# MCU_144_POWER.net
KiCad netlist of a schematic drawn in Altium Designer
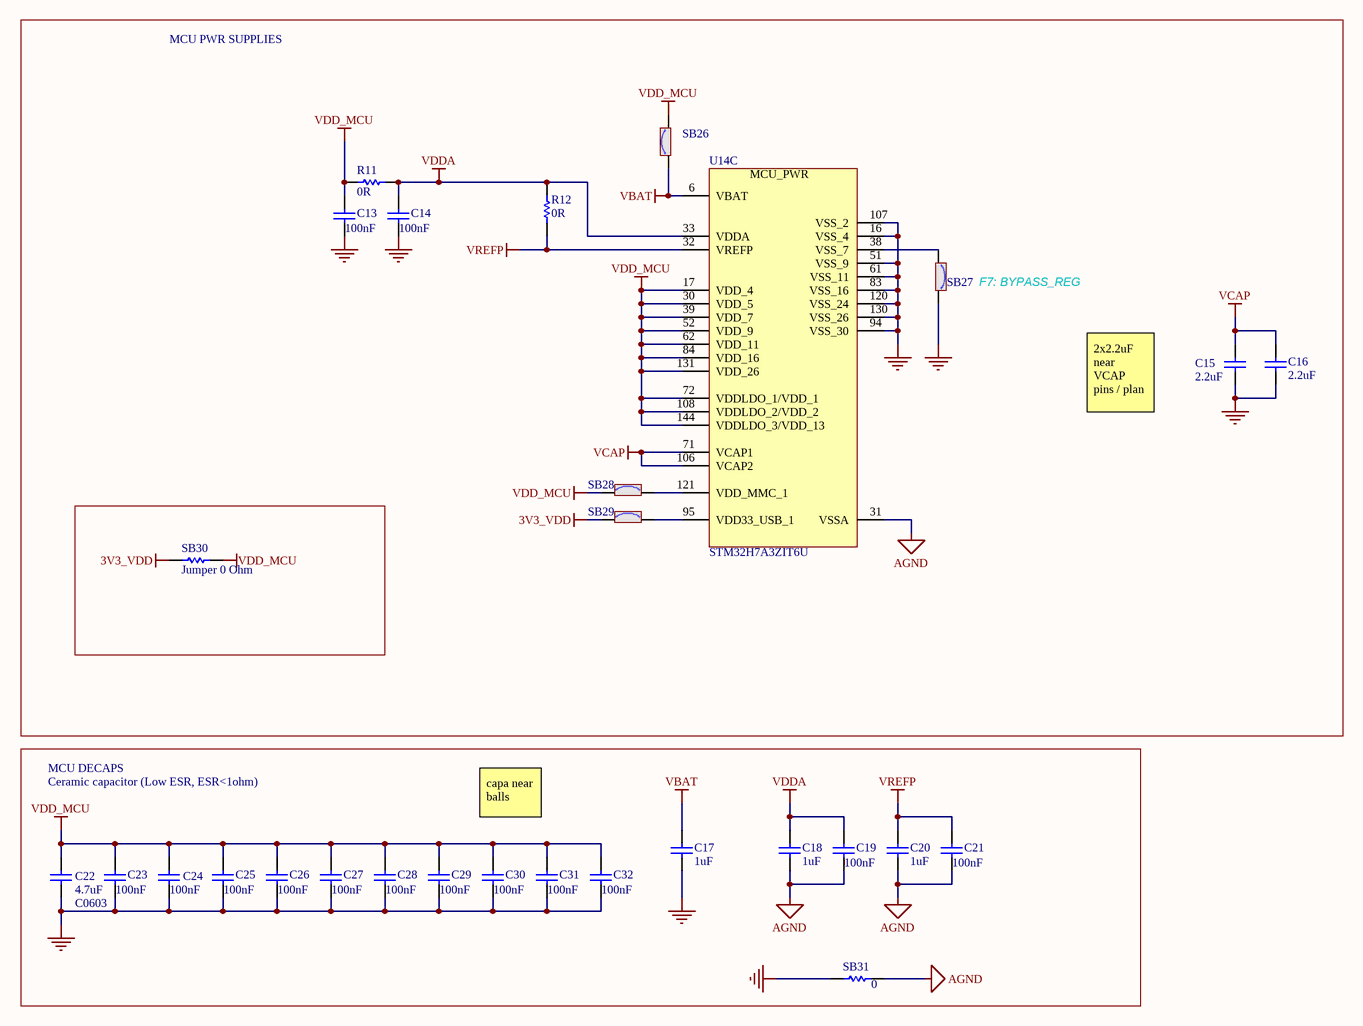
[diagram p0: MCU_144_POWER.SchDoc]

(export (version "E")
  (design (tool "Eeschema 10.0.6"))
  (components
    (comp (ref "C13")
      (value "Capacitor")
      (footprint "C0402")
      (description "CAP CER 0.1UF 16V X7R 0402")
      (fields
        (field (name "MANUFACTURER") "Yageo")
        (field (name "MANUFACTURER PART NUMBER") "CC0402KRX7R7BB104")
        (field (name "CAPACITANCE") "100nF")
      )
      (libsource (lib "MCD_PARTS_database") (part "Capacitor"))
    )
    (comp (ref "C14")
      (value "Capacitor")
      (footprint "C0402")
      (description "CAP CER 0.1UF 16V X7R 0402")
      (fields
        (field (name "MANUFACTURER") "Yageo")
        (field (name "MANUFACTURER PART NUMBER") "CC0402KRX7R7BB104")
        (field (name "CAPACITANCE") "100nF")
      )
      (libsource (lib "MCD_PARTS_database") (part "Capacitor"))
    )
    (comp (ref "C15")
      (value "2.2uF")
      (footprint "C0603")
      (description "Capacitor, MLCC, 2.2uF, 10V, X5R, 10%, 0603, T=0,8mm")
      (fields
        (field (name "INTERNAL_PART_NUMBER") "MCD-00012")
        (field (name "MANUFACTURER_PART_NUMBER") "CC0603KRX5R6BB225")
        (field (name "PROVIDED_BY") "SUBCO")
      )
      (libsource (lib "MCD_PARTS_database") (part "Capacitor"))
    )
    (comp (ref "C16")
      (value "2.2uF")
      (footprint "C0603")
      (description "Capacitor, MLCC, 2.2uF, 10V, X5R, 10%, 0603, T=0,8mm")
      (fields
        (field (name "INTERNAL_PART_NUMBER") "MCD-00012")
        (field (name "MANUFACTURER_PART_NUMBER") "CC0603KRX5R6BB225")
        (field (name "PROVIDED_BY") "SUBCO")
      )
      (libsource (lib "MCD_PARTS_database") (part "Capacitor"))
    )
    (comp (ref "C17")
      (value "1uF")
      (footprint "C0603")
      (description "Capacitor, MLCC, 1uF, 6V3, X5R, 10%, 0603, T=0,8mm")
      (fields
        (field (name "INTERNAL_PART_NUMBER") "MCD-00238")
        (field (name "MANUFACTURER_PART_NUMBER") "CC0603KRX5R5BB105")
        (field (name "PROVIDED_BY") "SUBCO")
      )
      (libsource (lib "MCD_PARTS_database") (part "Capacitor"))
    )
    (comp (ref "C18")
      (value "1uF")
      (footprint "C0603")
      (description "Capacitor, MLCC, 1uF, 6V3, X5R, 10%, 0603, T=0,8mm")
      (fields
        (field (name "INTERNAL_PART_NUMBER") "MCD-00238")
        (field (name "MANUFACTURER_PART_NUMBER") "CC0603KRX5R5BB105")
        (field (name "PROVIDED_BY") "SUBCO")
      )
      (libsource (lib "MCD_PARTS_database") (part "Capacitor"))
    )
    (comp (ref "C19")
      (value "Capacitor")
      (footprint "C0402")
      (description "CAP CER 0.1UF 16V X7R 0402")
      (fields
        (field (name "MANUFACTURER") "Yageo")
        (field (name "MANUFACTURER PART NUMBER") "CC0402KRX7R7BB104")
        (field (name "CAPACITANCE") "100nF")
      )
      (libsource (lib "MCD_PARTS_database") (part "Capacitor"))
    )
    (comp (ref "C20")
      (value "1uF")
      (footprint "C0603")
      (description "Capacitor, MLCC, 1uF, 6V3, X5R, 10%, 0603, T=0,8mm")
      (fields
        (field (name "INTERNAL_PART_NUMBER") "MCD-00238")
        (field (name "MANUFACTURER_PART_NUMBER") "CC0603KRX5R5BB105")
        (field (name "PROVIDED_BY") "SUBCO")
      )
      (libsource (lib "MCD_PARTS_database") (part "Capacitor"))
    )
    (comp (ref "C21")
      (value "Capacitor")
      (footprint "C0402")
      (description "CAP CER 0.1UF 16V X7R 0402")
      (fields
        (field (name "MANUFACTURER") "Yageo")
        (field (name "MANUFACTURER PART NUMBER") "CC0402KRX7R7BB104")
        (field (name "CAPACITANCE") "100nF")
      )
      (libsource (lib "MCD_PARTS_database") (part "Capacitor"))
    )
    (comp (ref "C22")
      (value "4.7uF")
      (footprint "C0603")
      (description "Capacitor, MLCC, 4.7µF, 10V, X5R, 20%, 0603, T=0,8mm")
      (fields
        (field (name "INTERNAL_PART_NUMBER") "MCD-01121")
        (field (name "MANUFACTURER_PART_NUMBER") "GRM188R61A475ME15")
        (field (name "PACKAGE") "C0603")
        (field (name "PROVIDED_BY") "SUBCO")
      )
      (libsource (lib "MCD_PARTS_database") (part "Capacitor"))
    )
    (comp (ref "C23")
      (value "Capacitor")
      (footprint "C0402")
      (description "CAP CER 0.1UF 16V X7R 0402")
      (fields
        (field (name "MANUFACTURER") "Yageo")
        (field (name "MANUFACTURER PART NUMBER") "CC0402KRX7R7BB104")
        (field (name "CAPACITANCE") "100nF")
      )
      (libsource (lib "MCD_PARTS_database") (part "Capacitor"))
    )
    (comp (ref "C24")
      (value "Capacitor")
      (footprint "C0402")
      (description "CAP CER 0.1UF 16V X7R 0402")
      (fields
        (field (name "MANUFACTURER") "Yageo")
        (field (name "MANUFACTURER PART NUMBER") "CC0402KRX7R7BB104")
        (field (name "CAPACITANCE") "100nF")
      )
      (libsource (lib "MCD_PARTS_database") (part "Capacitor"))
    )
    (comp (ref "C25")
      (value "Capacitor")
      (footprint "C0402")
      (description "CAP CER 0.1UF 16V X7R 0402")
      (fields
        (field (name "MANUFACTURER") "Yageo")
        (field (name "MANUFACTURER PART NUMBER") "CC0402KRX7R7BB104")
        (field (name "CAPACITANCE") "100nF")
      )
      (libsource (lib "MCD_PARTS_database") (part "Capacitor"))
    )
    (comp (ref "C26")
      (value "Capacitor")
      (footprint "C0402")
      (description "CAP CER 0.1UF 16V X7R 0402")
      (fields
        (field (name "MANUFACTURER") "Yageo")
        (field (name "MANUFACTURER PART NUMBER") "CC0402KRX7R7BB104")
        (field (name "CAPACITANCE") "100nF")
      )
      (libsource (lib "MCD_PARTS_database") (part "Capacitor"))
    )
    (comp (ref "C27")
      (value "Capacitor")
      (footprint "C0402")
      (description "CAP CER 0.1UF 16V X7R 0402")
      (fields
        (field (name "MANUFACTURER") "Yageo")
        (field (name "MANUFACTURER PART NUMBER") "CC0402KRX7R7BB104")
        (field (name "CAPACITANCE") "100nF")
      )
      (libsource (lib "MCD_PARTS_database") (part "Capacitor"))
    )
    (comp (ref "C28")
      (value "Capacitor")
      (footprint "C0402")
      (description "CAP CER 0.1UF 16V X7R 0402")
      (fields
        (field (name "MANUFACTURER") "Yageo")
        (field (name "MANUFACTURER PART NUMBER") "CC0402KRX7R7BB104")
        (field (name "CAPACITANCE") "100nF")
      )
      (libsource (lib "MCD_PARTS_database") (part "Capacitor"))
    )
    (comp (ref "C29")
      (value "Capacitor")
      (footprint "C0402")
      (description "CAP CER 0.1UF 16V X7R 0402")
      (fields
        (field (name "MANUFACTURER") "Yageo")
        (field (name "MANUFACTURER PART NUMBER") "CC0402KRX7R7BB104")
        (field (name "CAPACITANCE") "100nF")
      )
      (libsource (lib "MCD_PARTS_database") (part "Capacitor"))
    )
    (comp (ref "C30")
      (value "Capacitor")
      (footprint "C0402")
      (description "CAP CER 0.1UF 16V X7R 0402")
      (fields
        (field (name "MANUFACTURER") "Yageo")
        (field (name "MANUFACTURER PART NUMBER") "CC0402KRX7R7BB104")
        (field (name "CAPACITANCE") "100nF")
      )
      (libsource (lib "MCD_PARTS_database") (part "Capacitor"))
    )
    (comp (ref "C31")
      (value "Capacitor")
      (footprint "C0402")
      (description "CAP CER 0.1UF 16V X7R 0402")
      (fields
        (field (name "MANUFACTURER") "Yageo")
        (field (name "MANUFACTURER PART NUMBER") "CC0402KRX7R7BB104")
        (field (name "CAPACITANCE") "100nF")
      )
      (libsource (lib "MCD_PARTS_database") (part "Capacitor"))
    )
    (comp (ref "C32")
      (value "Capacitor")
      (footprint "C0402")
      (description "CAP CER 0.1UF 16V X7R 0402")
      (fields
        (field (name "MANUFACTURER") "Yageo")
        (field (name "MANUFACTURER PART NUMBER") "CC0402KRX7R7BB104")
        (field (name "CAPACITANCE") "100nF")
      )
      (libsource (lib "MCD_PARTS_database") (part "Capacitor"))
    )
    (comp (ref "R11")
      (value "0R")
      (footprint "R0603")
      (description "Resistor,0R,0603,5%,1/10W")
      (fields
        (field (name "INTERNAL_PART_NUMBER") "MCD-00056")
        (field (name "MANUFACTURER_PART_NUMBER") "RC0603JR-070RL")
        (field (name "PROVIDED_BY") "SUBCO")
      )
      (libsource (lib "MCD_PARTS_database") (part "Resistor"))
    )
    (comp (ref "R12")
      (value "0R")
      (footprint "R0603")
      (description "Resistor,0R,0603,5%,1/10W")
      (fields
        (field (name "INTERNAL_PART_NUMBER") "MCD-00056")
        (field (name "MANUFACTURER_PART_NUMBER") "RC0603JR-070RL")
        (field (name "PROVIDED_BY") "SUBCO")
      )
      (libsource (lib "MCD_PARTS_database") (part "Resistor"))
    )
    (comp (ref "SB26")
      (value "SB_ON")
      (footprint "SOLDER-BRIDGE_R0603-0R")
      (description "Solder Bridge ON")
      (fields
        (field (name "INTERNAL_PART_NUMBER") "MCD-00071")
        (field (name "MANUFACTURER_PART_NUMBER") "RC0603JR-070RL")
        (field (name "PROVIDED_BY") "SUBCO")
      )
      (libsource (lib "") (part "SB_ON_1"))
    )
    (comp (ref "SB27")
      (value "SB_ON")
      (footprint "SOLDER-BRIDGE_R0603-0R")
      (description "Solder Bridge ON")
      (fields
        (field (name "INTERNAL_PART_NUMBER") "MCD-00071")
        (field (name "MANUFACTURER_PART_NUMBER") "RC0603JR-070RL")
        (field (name "PROVIDED_BY") "SUBCO")
      )
      (libsource (lib "") (part "SB_ON_2"))
    )
    (comp (ref "SB28")
      (value "SB_ON")
      (footprint "SOLDER-BRIDGE_R0603-0R")
      (description "Solder Bridge ON")
      (fields
        (field (name "INTERNAL_PART_NUMBER") "MCD-00071")
        (field (name "MANUFACTURER_PART_NUMBER") "RC0603JR-070RL")
        (field (name "PROVIDED_BY") "SUBCO")
      )
      (libsource (lib "MCD_PARTS_database") (part "SB_ON"))
    )
    (comp (ref "SB29")
      (value "SB_ON")
      (footprint "SOLDER-BRIDGE_R0603-0R")
      (description "Solder Bridge ON")
      (fields
        (field (name "INTERNAL_PART_NUMBER") "MCD-00071")
        (field (name "MANUFACTURER_PART_NUMBER") "RC0603JR-070RL")
        (field (name "PROVIDED_BY") "SUBCO")
      )
      (libsource (lib "MCD_PARTS_database") (part "SB_ON"))
    )
    (comp (ref "SB30")
      (value "Jumper 0 Ohm")
      (footprint "RESC1608X55X25ML10T15")
      (description "Chip Resistor, 0 Ohm, +/- 5%, 0.1 W, -55 to 155 degC, 0603 (1608 Metric), RoHS, Tape and Reel")
      (fields (field (name "TOLERANCE") "5%") (field (name "MANUFACTURER") "Yageo"))
      (libsource (lib "Altium Content Vault") (part "RES-2"))
    )
    (comp (ref "SB31")
      (value "0")
      (footprint "RESC1608X55X25ML10T15")
      (description "Chip Resistor, 0 Ohm, +/- 5%, 0.1 W, -55 to 155 degC, 0603 (1608 Metric), RoHS, Tape and Reel")
      (fields (field (name "TOLERANCE") "5%") (field (name "MANUFACTURER") "Yageo"))
      (libsource (lib "Altium Content Vault") (part "RES-2"))
    )
    (comp (ref "U14")
      (value "STM32H7A3ZIT6U")
      (footprint "ICC_LQFP144_20X20_P050_SOCKET_YAMAICHI_IC149-144-145-B5_NM")
      (description "STM32H7A3ZIT6U, LQFP144 package, 20x20")
      (fields
        (field (name "INTERNAL_PART_NUMBER") "MCD-01349")
        (field (name "MANUFACTURER") "STMICROELECTRONICS")
        (field (name "PROVIDED_BY") "SUBCO with ST control")
      )
      (libsource (lib "MCD_PARTS_database") (part "STM32H7A3ZIT6"))
    )
  )
  (nets
    (net (code "1") (name "3V3_VDD") (class "Default")
      (node (ref "SB29") (pin "1") (pinfunction "1_1") (pintype "passive"))
      (node (ref "SB30") (pin "1") (pinfunction "1_1") (pintype "passive"))
    )
    (net (code "2") (name "AGND") (class "Default")
      (node (ref "C18") (pin "2") (pinfunction "2_2") (pintype "passive"))
      (node (ref "C19") (pin "1") (pinfunction "1_1") (pintype "passive"))
      (node (ref "C20") (pin "2") (pinfunction "2_2") (pintype "passive"))
      (node (ref "C21") (pin "1") (pinfunction "1_1") (pintype "passive"))
      (node (ref "SB31") (pin "2") (pinfunction "2_2") (pintype "passive"))
      (node (ref "U14") (pin "31") (pinfunction "VSSA_31") (pintype "passive"))
    )
    (net (code "3") (name "GND") (class "Default")
      (node (ref "C13") (pin "1") (pinfunction "1_1") (pintype "passive"))
      (node (ref "C14") (pin "1") (pinfunction "1_1") (pintype "passive"))
      (node (ref "C15") (pin "1") (pinfunction "1_1") (pintype "passive"))
      (node (ref "C16") (pin "1") (pinfunction "1_1") (pintype "passive"))
      (node (ref "C17") (pin "1") (pinfunction "1_1") (pintype "passive"))
      (node (ref "C22") (pin "1") (pinfunction "1_1") (pintype "passive"))
      (node (ref "C23") (pin "1") (pinfunction "1_1") (pintype "passive"))
      (node (ref "C24") (pin "1") (pinfunction "1_1") (pintype "passive"))
      (node (ref "C25") (pin "1") (pinfunction "1_1") (pintype "passive"))
      (node (ref "C26") (pin "1") (pinfunction "1_1") (pintype "passive"))
      (node (ref "C27") (pin "1") (pinfunction "1_1") (pintype "passive"))
      (node (ref "C28") (pin "1") (pinfunction "1_1") (pintype "passive"))
      (node (ref "C29") (pin "1") (pinfunction "1_1") (pintype "passive"))
      (node (ref "C30") (pin "1") (pinfunction "1_1") (pintype "passive"))
      (node (ref "C31") (pin "1") (pinfunction "1_1") (pintype "passive"))
      (node (ref "C32") (pin "1") (pinfunction "1_1") (pintype "passive"))
      (node (ref "SB27") (pin "2") (pinfunction "2_2") (pintype "passive"))
      (node (ref "SB31") (pin "1") (pinfunction "1_1") (pintype "passive"))
      (node (ref "U14") (pin "107") (pinfunction "VSS_2_107") (pintype "passive"))
      (node (ref "U14") (pin "120") (pinfunction "VSS_24_120") (pintype "passive"))
      (node (ref "U14") (pin "130") (pinfunction "VSS_26_130") (pintype "passive"))
      (node (ref "U14") (pin "16") (pinfunction "VSS_4_16") (pintype "passive"))
      (node (ref "U14") (pin "51") (pinfunction "VSS_9_51") (pintype "passive"))
      (node (ref "U14") (pin "61") (pinfunction "VSS_11_61") (pintype "passive"))
      (node (ref "U14") (pin "83") (pinfunction "VSS_16_83") (pintype "passive"))
      (node (ref "U14") (pin "94") (pinfunction "VSS_30_94") (pintype "passive"))
    )
    (net (code "4") (name "Net-(U14C-VDD33_USB_1)") (class "Default")
      (node (ref "SB29") (pin "2") (pinfunction "2_2") (pintype "passive"))
      (node (ref "U14") (pin "95") (pinfunction "VDD33_USB_1_95") (pintype "passive"))
    )
    (net (code "5") (name "Net-(U14C-VDD_MMC_1)") (class "Default")
      (node (ref "SB28") (pin "2") (pinfunction "2_2") (pintype "passive"))
      (node (ref "U14") (pin "121") (pinfunction "VDD_MMC_1_121") (pintype "passive"))
    )
    (net (code "6") (name "Net-(U14C-VSS_7)") (class "Default")
      (node (ref "SB27") (pin "1") (pinfunction "1_1") (pintype "passive"))
      (node (ref "U14") (pin "38") (pinfunction "VSS_7_38") (pintype "passive"))
    )
    (net (code "7") (name "VBAT") (class "Default")
      (node (ref "C17") (pin "2") (pinfunction "2_2") (pintype "passive"))
      (node (ref "SB26") (pin "1") (pinfunction "1_1") (pintype "passive"))
      (node (ref "U14") (pin "6") (pinfunction "VBAT_6") (pintype "passive"))
    )
    (net (code "8") (name "VCAP") (class "Default")
      (node (ref "C15") (pin "2") (pinfunction "2_2") (pintype "passive"))
      (node (ref "C16") (pin "2") (pinfunction "2_2") (pintype "passive"))
      (node (ref "U14") (pin "106") (pinfunction "VCAP2_106") (pintype "passive"))
      (node (ref "U14") (pin "71") (pinfunction "VCAP1_71") (pintype "passive"))
    )
    (net (code "9") (name "VDDA") (class "Default")
      (node (ref "C14") (pin "2") (pinfunction "2_2") (pintype "passive"))
      (node (ref "C18") (pin "1") (pinfunction "1_1") (pintype "passive"))
      (node (ref "C19") (pin "2") (pinfunction "2_2") (pintype "passive"))
      (node (ref "R11") (pin "2") (pinfunction "2_2") (pintype "passive"))
      (node (ref "R12") (pin "1") (pinfunction "1_1") (pintype "passive"))
      (node (ref "U14") (pin "33") (pinfunction "VDDA_33") (pintype "passive"))
    )
    (net (code "10") (name "VDD_MCU") (class "Default")
      (node (ref "C13") (pin "2") (pinfunction "2_2") (pintype "passive"))
      (node (ref "C22") (pin "2") (pinfunction "2_2") (pintype "passive"))
      (node (ref "C23") (pin "2") (pinfunction "2_2") (pintype "passive"))
      (node (ref "C24") (pin "2") (pinfunction "2_2") (pintype "passive"))
      (node (ref "C25") (pin "2") (pinfunction "2_2") (pintype "passive"))
      (node (ref "C26") (pin "2") (pinfunction "2_2") (pintype "passive"))
      (node (ref "C27") (pin "2") (pinfunction "2_2") (pintype "passive"))
      (node (ref "C28") (pin "2") (pinfunction "2_2") (pintype "passive"))
      (node (ref "C29") (pin "2") (pinfunction "2_2") (pintype "passive"))
      (node (ref "C30") (pin "2") (pinfunction "2_2") (pintype "passive"))
      (node (ref "C31") (pin "2") (pinfunction "2_2") (pintype "passive"))
      (node (ref "C32") (pin "2") (pinfunction "2_2") (pintype "passive"))
      (node (ref "R11") (pin "1") (pinfunction "1_1") (pintype "passive"))
      (node (ref "SB26") (pin "2") (pinfunction "2_2") (pintype "passive"))
      (node (ref "SB28") (pin "1") (pinfunction "1_1") (pintype "passive"))
      (node (ref "SB30") (pin "2") (pinfunction "2_2") (pintype "passive"))
      (node (ref "U14") (pin "108") (pinfunction "VDDLDO_2/VDD_2_108") (pintype "passive"))
      (node (ref "U14") (pin "131") (pinfunction "VDD_26_131") (pintype "passive"))
      (node (ref "U14") (pin "144") (pinfunction "VDDLDO_3/VDD_13_144") (pintype "passive"))
      (node (ref "U14") (pin "17") (pinfunction "VDD_4_17") (pintype "passive"))
      (node (ref "U14") (pin "30") (pinfunction "VDD_5_30") (pintype "passive"))
      (node (ref "U14") (pin "39") (pinfunction "VDD_7_39") (pintype "passive"))
      (node (ref "U14") (pin "52") (pinfunction "VDD_9_52") (pintype "passive"))
      (node (ref "U14") (pin "62") (pinfunction "VDD_11_62") (pintype "passive"))
      (node (ref "U14") (pin "72") (pinfunction "VDDLDO_1/VDD_1_72") (pintype "passive"))
      (node (ref "U14") (pin "84") (pinfunction "VDD_16_84") (pintype "passive"))
    )
    (net (code "11") (name "VREFP") (class "Default")
      (node (ref "C20") (pin "1") (pinfunction "1_1") (pintype "passive"))
      (node (ref "C21") (pin "2") (pinfunction "2_2") (pintype "passive"))
      (node (ref "R12") (pin "2") (pinfunction "2_2") (pintype "passive"))
      (node (ref "U14") (pin "32") (pinfunction "VREFP_32") (pintype "passive"))
    )
  )
)
